# Goldfinger_Connector.net
KiCad netlist of a schematic drawn in Altium Designer
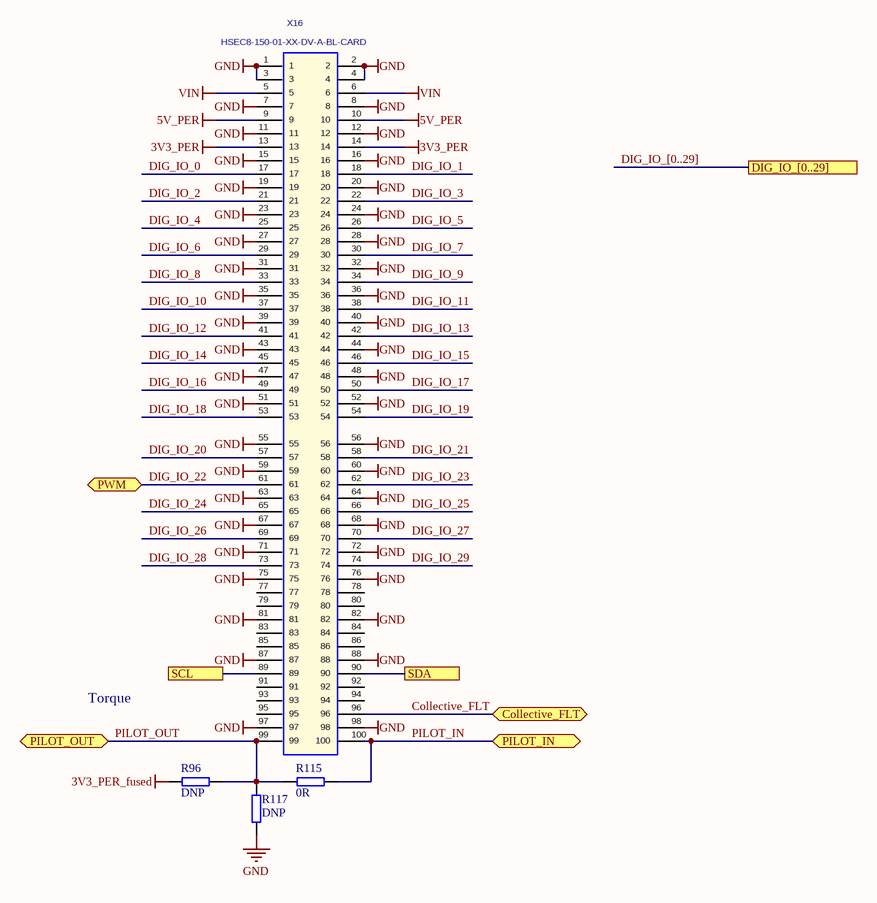
[diagram p0: Goldfinger_Connector.SchDoc]

(export (version "E")
  (design (tool "Eeschema 10.0.6"))
  (components
    (comp (ref "R96")
      (value "DNP")
      (footprint "RESC1608X06N")
      (fields (field (name "MF") "Vishay") (field (name "MPN") "CRCW06030000Z0EAC"))
      (libsource (lib "UltraZohm_ADC") (part "R_0603"))
    )
    (comp (ref "R115")
      (value "0R")
      (footprint "RESC1608X06N")
      (fields (field (name "MF") "Vishay") (field (name "MPN") "CRCW06030000Z0EAC"))
      (libsource (lib "UltraZohm_ADC") (part "R_0603"))
    )
    (comp (ref "R117")
      (value "DNP")
      (footprint "RESC1608X06N")
      (fields (field (name "MF") "Vishay") (field (name "MPN") "CRCW06030000Z0EAC"))
      (libsource (lib "UltraZohm_ADC") (part "R_0603"))
    )
    (comp (ref "X16")
      (value "HSEC8-150-01-XX-DV-A-BL-CARD")
      (footprint "HSEC8-150-01-XX-DV-A-BL-CARD")
      (description "Mating Card Layout for HSEC8-150-01-XX-DV-A-BL")
      (fields (field (name "MANUFACTURER") "SAMTEC") (field (name "CREATED") "2018_04_23_AGeiger"))
      (libsource (lib "Samtec") (part "HSEC8-150-01-XX-DV-A-BL-CARD"))
    )
  )
  (nets
    (net (code "1") (name "/Collective_FLT") (class "Default")
      (node (ref "X16") (pin "96") (pinfunction "96_96") (pintype "passive"))
    )
    (net (code "2") (name "/DIG_IO_0") (class "Default")
      (node (ref "X16") (pin "17") (pinfunction "17_17") (pintype "passive"))
    )
    (net (code "3") (name "/DIG_IO_1") (class "Default")
      (node (ref "X16") (pin "18") (pinfunction "18_18") (pintype "passive"))
    )
    (net (code "4") (name "/DIG_IO_2") (class "Default")
      (node (ref "X16") (pin "21") (pinfunction "21_21") (pintype "passive"))
    )
    (net (code "5") (name "/DIG_IO_3") (class "Default")
      (node (ref "X16") (pin "22") (pinfunction "22_22") (pintype "passive"))
    )
    (net (code "6") (name "/DIG_IO_4") (class "Default")
      (node (ref "X16") (pin "25") (pinfunction "25_25") (pintype "passive"))
    )
    (net (code "7") (name "/DIG_IO_5") (class "Default")
      (node (ref "X16") (pin "26") (pinfunction "26_26") (pintype "passive"))
    )
    (net (code "8") (name "/DIG_IO_6") (class "Default")
      (node (ref "X16") (pin "29") (pinfunction "29_29") (pintype "passive"))
    )
    (net (code "9") (name "/DIG_IO_7") (class "Default")
      (node (ref "X16") (pin "30") (pinfunction "30_30") (pintype "passive"))
    )
    (net (code "10") (name "/DIG_IO_8") (class "Default")
      (node (ref "X16") (pin "33") (pinfunction "33_33") (pintype "passive"))
    )
    (net (code "11") (name "/DIG_IO_9") (class "Default")
      (node (ref "X16") (pin "34") (pinfunction "34_34") (pintype "passive"))
    )
    (net (code "12") (name "/DIG_IO_10") (class "Default")
      (node (ref "X16") (pin "37") (pinfunction "37_37") (pintype "passive"))
    )
    (net (code "13") (name "/DIG_IO_11") (class "Default")
      (node (ref "X16") (pin "38") (pinfunction "38_38") (pintype "passive"))
    )
    (net (code "14") (name "/DIG_IO_12") (class "Default")
      (node (ref "X16") (pin "41") (pinfunction "41_41") (pintype "passive"))
    )
    (net (code "15") (name "/DIG_IO_13") (class "Default")
      (node (ref "X16") (pin "42") (pinfunction "42_42") (pintype "passive"))
    )
    (net (code "16") (name "/DIG_IO_14") (class "Default")
      (node (ref "X16") (pin "45") (pinfunction "45_45") (pintype "passive"))
    )
    (net (code "17") (name "/DIG_IO_15") (class "Default")
      (node (ref "X16") (pin "46") (pinfunction "46_46") (pintype "passive"))
    )
    (net (code "18") (name "/DIG_IO_16") (class "Default")
      (node (ref "X16") (pin "49") (pinfunction "49_49") (pintype "passive"))
    )
    (net (code "19") (name "/DIG_IO_17") (class "Default")
      (node (ref "X16") (pin "50") (pinfunction "50_50") (pintype "passive"))
    )
    (net (code "20") (name "/DIG_IO_18") (class "Default")
      (node (ref "X16") (pin "53") (pinfunction "53_53") (pintype "passive"))
    )
    (net (code "21") (name "/DIG_IO_19") (class "Default")
      (node (ref "X16") (pin "54") (pinfunction "54_54") (pintype "passive"))
    )
    (net (code "22") (name "/DIG_IO_20") (class "Default")
      (node (ref "X16") (pin "57") (pinfunction "57_57") (pintype "passive"))
    )
    (net (code "23") (name "/DIG_IO_21") (class "Default")
      (node (ref "X16") (pin "58") (pinfunction "58_58") (pintype "passive"))
    )
    (net (code "24") (name "/DIG_IO_22") (class "Default")
      (node (ref "X16") (pin "61") (pinfunction "61_61") (pintype "passive"))
    )
    (net (code "25") (name "/DIG_IO_23") (class "Default")
      (node (ref "X16") (pin "62") (pinfunction "62_62") (pintype "passive"))
    )
    (net (code "26") (name "/DIG_IO_24") (class "Default")
      (node (ref "X16") (pin "65") (pinfunction "65_65") (pintype "passive"))
    )
    (net (code "27") (name "/DIG_IO_25") (class "Default")
      (node (ref "X16") (pin "66") (pinfunction "66_66") (pintype "passive"))
    )
    (net (code "28") (name "/DIG_IO_26") (class "Default")
      (node (ref "X16") (pin "69") (pinfunction "69_69") (pintype "passive"))
    )
    (net (code "29") (name "/DIG_IO_27") (class "Default")
      (node (ref "X16") (pin "70") (pinfunction "70_70") (pintype "passive"))
    )
    (net (code "30") (name "/DIG_IO_28") (class "Default")
      (node (ref "X16") (pin "73") (pinfunction "73_73") (pintype "passive"))
    )
    (net (code "31") (name "/DIG_IO_29") (class "Default")
      (node (ref "X16") (pin "74") (pinfunction "74_74") (pintype "passive"))
    )
    (net (code "33") (name "/PILOT_IN") (class "Default")
      (node (ref "R115") (pin "2") (pintype "passive"))
      (node (ref "X16") (pin "100") (pinfunction "100_100") (pintype "passive"))
    )
    (net (code "34") (name "/PILOT_OUT") (class "Default")
      (node (ref "R115") (pin "1") (pintype "passive"))
      (node (ref "R117") (pin "2") (pintype "passive"))
      (node (ref "R96") (pin "1") (pintype "passive"))
      (node (ref "X16") (pin "99") (pinfunction "99_99") (pintype "passive"))
    )
    (net (code "35") (name "/SCL") (class "Default")
      (node (ref "X16") (pin "89") (pinfunction "89_89") (pintype "passive"))
    )
    (net (code "36") (name "/SDA") (class "Default")
      (node (ref "X16") (pin "90") (pinfunction "90_90") (pintype "passive"))
    )
    (net (code "37") (name "3V3_PER") (class "Default")
      (node (ref "X16") (pin "13") (pinfunction "13_13") (pintype "passive"))
      (node (ref "X16") (pin "14") (pinfunction "14_14") (pintype "passive"))
    )
    (net (code "38") (name "3V3_PER_fused") (class "Default")
      (node (ref "R96") (pin "2") (pintype "passive"))
    )
    (net (code "39") (name "5V_PER") (class "Default")
      (node (ref "X16") (pin "10") (pinfunction "10_10") (pintype "passive"))
      (node (ref "X16") (pin "9") (pinfunction "9_9") (pintype "passive"))
    )
    (net (code "40") (name "GND") (class "Default")
      (node (ref "R117") (pin "1") (pintype "passive"))
      (node (ref "X16") (pin "1") (pinfunction "1_1") (pintype "passive"))
      (node (ref "X16") (pin "11") (pinfunction "11_11") (pintype "passive"))
      (node (ref "X16") (pin "12") (pinfunction "12_12") (pintype "passive"))
      (node (ref "X16") (pin "15") (pinfunction "15_15") (pintype "passive"))
      (node (ref "X16") (pin "16") (pinfunction "16_16") (pintype "passive"))
      (node (ref "X16") (pin "19") (pinfunction "19_19") (pintype "passive"))
      (node (ref "X16") (pin "2") (pinfunction "2_2") (pintype "passive"))
      (node (ref "X16") (pin "20") (pinfunction "20_20") (pintype "passive"))
      (node (ref "X16") (pin "23") (pinfunction "23_23") (pintype "passive"))
      (node (ref "X16") (pin "24") (pinfunction "24_24") (pintype "passive"))
      (node (ref "X16") (pin "27") (pinfunction "27_27") (pintype "passive"))
      (node (ref "X16") (pin "28") (pinfunction "28_28") (pintype "passive"))
      (node (ref "X16") (pin "3") (pinfunction "3_3") (pintype "passive"))
      (node (ref "X16") (pin "31") (pinfunction "31_31") (pintype "passive"))
      (node (ref "X16") (pin "32") (pinfunction "32_32") (pintype "passive"))
      (node (ref "X16") (pin "35") (pinfunction "35_35") (pintype "passive"))
      (node (ref "X16") (pin "36") (pinfunction "36_36") (pintype "passive"))
      (node (ref "X16") (pin "39") (pinfunction "39_39") (pintype "passive"))
      (node (ref "X16") (pin "4") (pinfunction "4_4") (pintype "passive"))
      (node (ref "X16") (pin "40") (pinfunction "40_40") (pintype "passive"))
      (node (ref "X16") (pin "43") (pinfunction "43_43") (pintype "passive"))
      (node (ref "X16") (pin "44") (pinfunction "44_44") (pintype "passive"))
      (node (ref "X16") (pin "47") (pinfunction "47_47") (pintype "passive"))
      (node (ref "X16") (pin "48") (pinfunction "48_48") (pintype "passive"))
      (node (ref "X16") (pin "51") (pinfunction "51_51") (pintype "passive"))
      (node (ref "X16") (pin "52") (pinfunction "52_52") (pintype "passive"))
      (node (ref "X16") (pin "55") (pinfunction "55_55") (pintype "passive"))
      (node (ref "X16") (pin "56") (pinfunction "56_56") (pintype "passive"))
      (node (ref "X16") (pin "59") (pinfunction "59_59") (pintype "passive"))
      (node (ref "X16") (pin "60") (pinfunction "60_60") (pintype "passive"))
      (node (ref "X16") (pin "63") (pinfunction "63_63") (pintype "passive"))
      (node (ref "X16") (pin "64") (pinfunction "64_64") (pintype "passive"))
      (node (ref "X16") (pin "67") (pinfunction "67_67") (pintype "passive"))
      (node (ref "X16") (pin "68") (pinfunction "68_68") (pintype "passive"))
      (node (ref "X16") (pin "7") (pinfunction "7_7") (pintype "passive"))
      (node (ref "X16") (pin "71") (pinfunction "71_71") (pintype "passive"))
      (node (ref "X16") (pin "72") (pinfunction "72_72") (pintype "passive"))
      (node (ref "X16") (pin "75") (pinfunction "75_75") (pintype "passive"))
      (node (ref "X16") (pin "76") (pinfunction "76_76") (pintype "passive"))
      (node (ref "X16") (pin "8") (pinfunction "8_8") (pintype "passive"))
      (node (ref "X16") (pin "81") (pinfunction "81_81") (pintype "passive"))
      (node (ref "X16") (pin "82") (pinfunction "82_82") (pintype "passive"))
      (node (ref "X16") (pin "87") (pinfunction "87_87") (pintype "passive"))
      (node (ref "X16") (pin "88") (pinfunction "88_88") (pintype "passive"))
      (node (ref "X16") (pin "97") (pinfunction "97_97") (pintype "passive"))
      (node (ref "X16") (pin "98") (pinfunction "98_98") (pintype "passive"))
    )
    (net (code "41") (name "VIN") (class "Default")
      (node (ref "X16") (pin "5") (pinfunction "5_5") (pintype "passive"))
      (node (ref "X16") (pin "6") (pinfunction "6_6") (pintype "passive"))
    )
    (net (code "42") (name "unconnected-(X16-Pad77)") (class "Default")
      (node (ref "X16") (pin "77") (pinfunction "77_77") (pintype "passive"))
    )
    (net (code "43") (name "unconnected-(X16-Pad78)") (class "Default")
      (node (ref "X16") (pin "78") (pinfunction "78_78") (pintype "passive"))
    )
    (net (code "44") (name "unconnected-(X16-Pad79)") (class "Default")
      (node (ref "X16") (pin "79") (pinfunction "79_79") (pintype "passive"))
    )
    (net (code "45") (name "unconnected-(X16-Pad80)") (class "Default")
      (node (ref "X16") (pin "80") (pinfunction "80_80") (pintype "passive"))
    )
    (net (code "46") (name "unconnected-(X16-Pad83)") (class "Default")
      (node (ref "X16") (pin "83") (pinfunction "83_83") (pintype "passive"))
    )
    (net (code "47") (name "unconnected-(X16-Pad84)") (class "Default")
      (node (ref "X16") (pin "84") (pinfunction "84_84") (pintype "passive"))
    )
    (net (code "48") (name "unconnected-(X16-Pad85)") (class "Default")
      (node (ref "X16") (pin "85") (pinfunction "85_85") (pintype "passive"))
    )
    (net (code "49") (name "unconnected-(X16-Pad86)") (class "Default")
      (node (ref "X16") (pin "86") (pinfunction "86_86") (pintype "passive"))
    )
    (net (code "50") (name "unconnected-(X16-Pad91)") (class "Default")
      (node (ref "X16") (pin "91") (pinfunction "91_91") (pintype "passive"))
    )
    (net (code "51") (name "unconnected-(X16-Pad92)") (class "Default")
      (node (ref "X16") (pin "92") (pinfunction "92_92") (pintype "passive"))
    )
    (net (code "52") (name "unconnected-(X16-Pad93)") (class "Default")
      (node (ref "X16") (pin "93") (pinfunction "93_93") (pintype "passive"))
    )
    (net (code "53") (name "unconnected-(X16-Pad94)") (class "Default")
      (node (ref "X16") (pin "94") (pinfunction "94_94") (pintype "passive"))
    )
    (net (code "54") (name "unconnected-(X16-Pad95)") (class "Default")
      (node (ref "X16") (pin "95") (pinfunction "95_95") (pintype "passive"))
    )
  )
)
